# microfono_v1_rev1.net
KiCad netlist of a schematic drawn in EAGLE
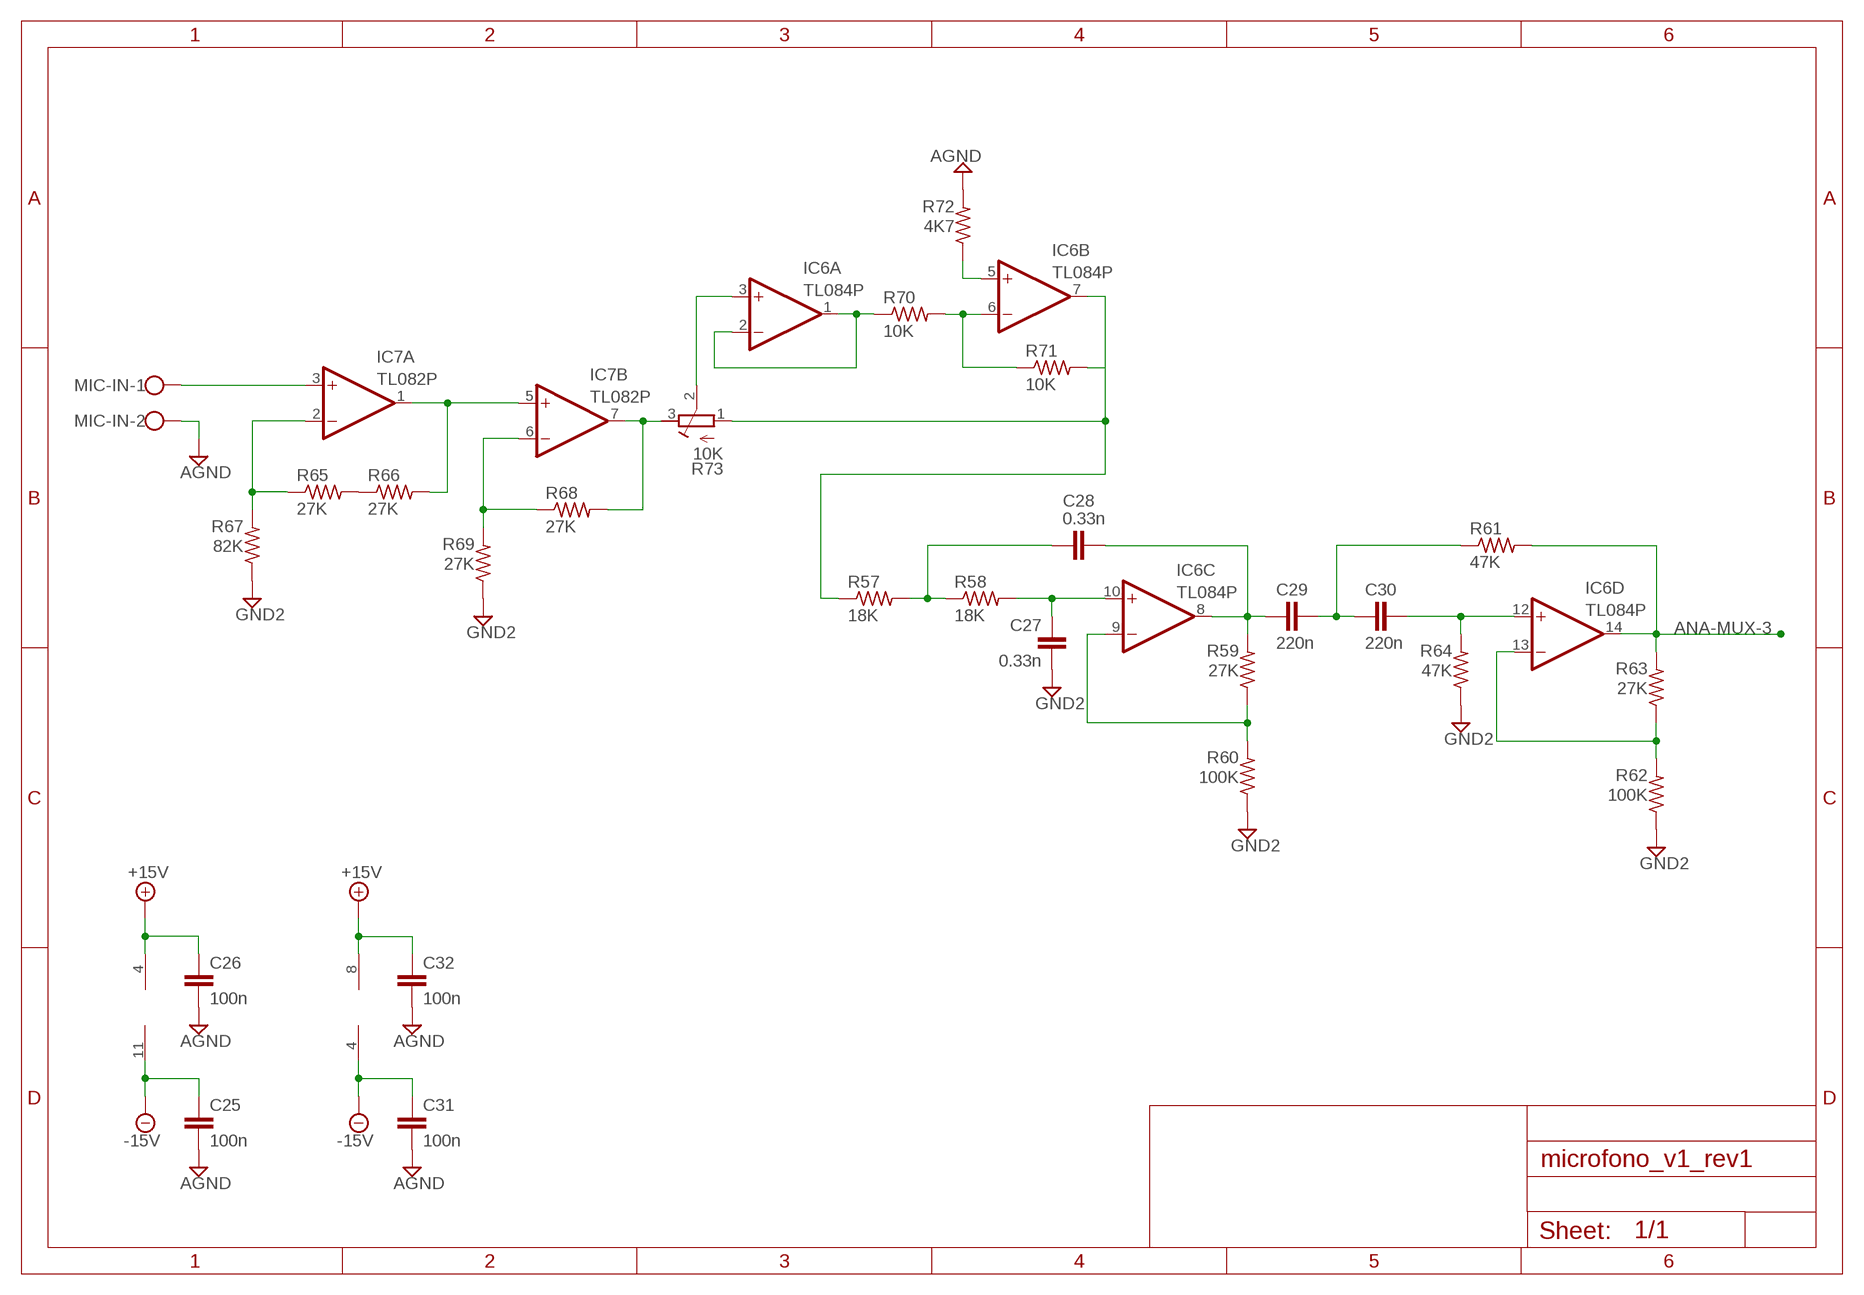
[diagram p0: schematic, sheet 1]

(export (version "E")
  (design (tool "Eeschema 10.0.6"))
  (components
    (comp (ref "C25")
      (value "100n")
      (footprint "eagle-import:C025-025X050")
      (libsource (lib "eagle-import") (part "C-EU025-025X050"))
    )
    (comp (ref "C26")
      (value "100n")
      (footprint "eagle-import:C025-025X050")
      (libsource (lib "eagle-import") (part "C-EU025-025X050"))
    )
    (comp (ref "C27")
      (value "0.33n")
      (footprint "eagle-import:C025-025X050")
      (libsource (lib "eagle-import") (part "C-EU025-025X050"))
    )
    (comp (ref "C28")
      (value "0.33n")
      (footprint "eagle-import:C025-025X050")
      (libsource (lib "eagle-import") (part "C-EU025-025X050"))
    )
    (comp (ref "C29")
      (value "220n")
      (footprint "eagle-import:C025-025X050")
      (libsource (lib "eagle-import") (part "C-EU025-025X050"))
    )
    (comp (ref "C30")
      (value "220n")
      (footprint "eagle-import:C025-025X050")
      (libsource (lib "eagle-import") (part "C-EU025-025X050"))
    )
    (comp (ref "C31")
      (value "100n")
      (footprint "eagle-import:C025-025X050")
      (libsource (lib "eagle-import") (part "C-EU025-025X050"))
    )
    (comp (ref "C32")
      (value "100n")
      (footprint "eagle-import:C025-025X050")
      (libsource (lib "eagle-import") (part "C-EU025-025X050"))
    )
    (comp (ref "IC6")
      (value "TL084P")
      (footprint "eagle-import:DIL14")
      (libsource (lib "eagle-import") (part "TL084P"))
    )
    (comp (ref "IC7")
      (value "TL082P")
      (footprint "eagle-import:DIL08")
      (libsource (lib "eagle-import") (part "TL082P"))
    )
    (comp (ref "MIC-IN")
      (value "W237-102")
      (footprint "eagle-import:W237-102")
      (fields (field (name "MPN") "237-102"))
      (libsource (lib "eagle-import") (part "W237-102"))
    )
    (comp (ref "R57")
      (value "18K")
      (footprint "eagle-import:0204_7")
      (libsource (lib "eagle-import") (part "R-US_0204/7"))
    )
    (comp (ref "R58")
      (value "18K")
      (footprint "eagle-import:0204_7")
      (libsource (lib "eagle-import") (part "R-US_0204/7"))
    )
    (comp (ref "R59")
      (value "27K")
      (footprint "eagle-import:0204_7")
      (libsource (lib "eagle-import") (part "R-US_0204/7"))
    )
    (comp (ref "R60")
      (value "100K")
      (footprint "eagle-import:0204_7")
      (libsource (lib "eagle-import") (part "R-US_0204/7"))
    )
    (comp (ref "R61")
      (value "47K")
      (footprint "eagle-import:0204_7")
      (libsource (lib "eagle-import") (part "R-US_0204/7"))
    )
    (comp (ref "R62")
      (value "100K")
      (footprint "eagle-import:0204_7")
      (libsource (lib "eagle-import") (part "R-US_0204/7"))
    )
    (comp (ref "R63")
      (value "27K")
      (footprint "eagle-import:0204_7")
      (libsource (lib "eagle-import") (part "R-US_0204/7"))
    )
    (comp (ref "R64")
      (value "47K")
      (footprint "eagle-import:0204_7")
      (libsource (lib "eagle-import") (part "R-US_0204/7"))
    )
    (comp (ref "R65")
      (value "27K")
      (footprint "eagle-import:0204_7")
      (libsource (lib "eagle-import") (part "R-US_0204/7"))
    )
    (comp (ref "R66")
      (value "27K")
      (footprint "eagle-import:0204_7")
      (libsource (lib "eagle-import") (part "R-US_0204/7"))
    )
    (comp (ref "R67")
      (value "82K")
      (footprint "eagle-import:0204_7")
      (libsource (lib "eagle-import") (part "R-US_0204/7"))
    )
    (comp (ref "R68")
      (value "27K")
      (footprint "eagle-import:0204_7")
      (libsource (lib "eagle-import") (part "R-US_0204/7"))
    )
    (comp (ref "R69")
      (value "27K")
      (footprint "eagle-import:0204_7")
      (libsource (lib "eagle-import") (part "R-US_0204/7"))
    )
    (comp (ref "R70")
      (value "10K")
      (footprint "eagle-import:0204_7")
      (libsource (lib "eagle-import") (part "R-US_0204/7"))
    )
    (comp (ref "R71")
      (value "10K")
      (footprint "eagle-import:0204_7")
      (libsource (lib "eagle-import") (part "R-US_0204/7"))
    )
    (comp (ref "R72")
      (value "4K7")
      (footprint "eagle-import:0204_7")
      (libsource (lib "eagle-import") (part "R-US_0204/7"))
    )
    (comp (ref "R73")
      (value "10K")
      (footprint "eagle-import:RTRIM64W")
      (libsource (lib "eagle-import") (part "R-TRIMM64W"))
    )
  )
  (nets
    (net (code "1") (name "+15V") (class "Default")
      (node (ref "C26") (pin "1") (pinfunction "1_1") (pintype "passive"))
      (node (ref "C32") (pin "1") (pinfunction "1_1") (pintype "passive"))
      (node (ref "IC6") (pin "4") (pinfunction "V+_4") (pintype "power_in"))
      (node (ref "IC7") (pin "8") (pinfunction "V+_8") (pintype "power_in"))
    )
    (net (code "2") (name "-15V") (class "Default")
      (node (ref "C25") (pin "1") (pinfunction "1_1") (pintype "passive"))
      (node (ref "C31") (pin "1") (pinfunction "1_1") (pintype "passive"))
      (node (ref "IC6") (pin "11") (pinfunction "V-_11") (pintype "power_in"))
      (node (ref "IC7") (pin "4") (pinfunction "V-_4") (pintype "power_in"))
    )
    (net (code "3") (name "/ANA-MUX-3") (class "Default")
      (node (ref "IC6") (pin "14") (pinfunction "OUT_14") (pintype "output"))
      (node (ref "R61") (pin "2") (pinfunction "2_2") (pintype "passive"))
      (node (ref "R63") (pin "2") (pinfunction "2_2") (pintype "passive"))
    )
    (net (code "4") (name "AGND") (class "Default")
      (node (ref "C25") (pin "2") (pinfunction "2_2") (pintype "passive"))
      (node (ref "C26") (pin "2") (pinfunction "2_2") (pintype "passive"))
      (node (ref "C31") (pin "2") (pinfunction "2_2") (pintype "passive"))
      (node (ref "C32") (pin "2") (pinfunction "2_2") (pintype "passive"))
      (node (ref "MIC-IN") (pin "2") (pinfunction "KL_2") (pintype "passive"))
      (node (ref "R72") (pin "2") (pinfunction "2_2") (pintype "passive"))
    )
    (net (code "5") (name "GND2") (class "Default")
      (node (ref "C27") (pin "2") (pinfunction "2_2") (pintype "passive"))
      (node (ref "R60") (pin "1") (pinfunction "1_1") (pintype "passive"))
      (node (ref "R62") (pin "1") (pinfunction "1_1") (pintype "passive"))
      (node (ref "R64") (pin "1") (pinfunction "1_1") (pintype "passive"))
      (node (ref "R67") (pin "1") (pinfunction "1_1") (pintype "passive"))
      (node (ref "R69") (pin "1") (pinfunction "1_1") (pintype "passive"))
    )
    (net (code "6") (name "Net-(C28-Pad1)") (class "Default")
      (node (ref "C28") (pin "1") (pinfunction "1_1") (pintype "passive"))
      (node (ref "R57") (pin "2") (pinfunction "2_2") (pintype "passive"))
      (node (ref "R58") (pin "1") (pinfunction "1_1") (pintype "passive"))
    )
    (net (code "7") (name "Net-(C29-Pad2)") (class "Default")
      (node (ref "C29") (pin "2") (pinfunction "2_2") (pintype "passive"))
      (node (ref "C30") (pin "1") (pinfunction "1_1") (pintype "passive"))
      (node (ref "R61") (pin "1") (pinfunction "1_1") (pintype "passive"))
    )
    (net (code "8") (name "Net-(IC6A-+IN)") (class "Default")
      (node (ref "IC6") (pin "3") (pinfunction "+IN_3") (pintype "input"))
      (node (ref "R73") (pin "2") (pinfunction "S_2") (pintype "passive"))
    )
    (net (code "9") (name "Net-(IC6A--IN)") (class "Default")
      (node (ref "IC6") (pin "1") (pinfunction "OUT_1") (pintype "output"))
      (node (ref "IC6") (pin "2") (pinfunction "-IN_2") (pintype "input"))
      (node (ref "R70") (pin "1") (pinfunction "1_1") (pintype "passive"))
    )
    (net (code "10") (name "Net-(IC6B-+IN)") (class "Default")
      (node (ref "IC6") (pin "5") (pinfunction "+IN_5") (pintype "input"))
      (node (ref "R72") (pin "1") (pinfunction "1_1") (pintype "passive"))
    )
    (net (code "11") (name "Net-(IC6B--IN)") (class "Default")
      (node (ref "IC6") (pin "6") (pinfunction "-IN_6") (pintype "input"))
      (node (ref "R70") (pin "2") (pinfunction "2_2") (pintype "passive"))
      (node (ref "R71") (pin "1") (pinfunction "1_1") (pintype "passive"))
    )
    (net (code "12") (name "Net-(IC6B-OUT)") (class "Default")
      (node (ref "IC6") (pin "7") (pinfunction "OUT_7") (pintype "output"))
      (node (ref "R57") (pin "1") (pinfunction "1_1") (pintype "passive"))
      (node (ref "R73") (pin "1") (pinfunction "A_1") (pintype "passive"))
    )
    (net (code "13") (name "Net-(IC6C-+IN)") (class "Default")
      (node (ref "C27") (pin "1") (pinfunction "1_1") (pintype "passive"))
      (node (ref "IC6") (pin "10") (pinfunction "+IN_10") (pintype "input"))
      (node (ref "R58") (pin "2") (pinfunction "2_2") (pintype "passive"))
    )
    (net (code "14") (name "Net-(IC6C--IN)") (class "Default")
      (node (ref "IC6") (pin "9") (pinfunction "-IN_9") (pintype "input"))
      (node (ref "R59") (pin "1") (pinfunction "1_1") (pintype "passive"))
      (node (ref "R60") (pin "2") (pinfunction "2_2") (pintype "passive"))
    )
    (net (code "15") (name "Net-(IC6C-OUT)") (class "Default")
      (node (ref "C28") (pin "2") (pinfunction "2_2") (pintype "passive"))
      (node (ref "C29") (pin "1") (pinfunction "1_1") (pintype "passive"))
      (node (ref "IC6") (pin "8") (pinfunction "OUT_8") (pintype "output"))
      (node (ref "R59") (pin "2") (pinfunction "2_2") (pintype "passive"))
    )
    (net (code "16") (name "Net-(IC6D-+IN)") (class "Default")
      (node (ref "C30") (pin "2") (pinfunction "2_2") (pintype "passive"))
      (node (ref "IC6") (pin "12") (pinfunction "+IN_12") (pintype "input"))
      (node (ref "R64") (pin "2") (pinfunction "2_2") (pintype "passive"))
    )
    (net (code "17") (name "Net-(IC6D--IN)") (class "Default")
      (node (ref "IC6") (pin "13") (pinfunction "-IN_13") (pintype "input"))
      (node (ref "R62") (pin "2") (pinfunction "2_2") (pintype "passive"))
      (node (ref "R63") (pin "1") (pinfunction "1_1") (pintype "passive"))
    )
    (net (code "18") (name "Net-(IC7A-+IN)") (class "Default")
      (node (ref "IC7") (pin "3") (pinfunction "+IN_3") (pintype "input"))
      (node (ref "MIC-IN") (pin "1") (pinfunction "KL_1") (pintype "passive"))
    )
    (net (code "19") (name "Net-(IC7A--IN)") (class "Default")
      (node (ref "IC7") (pin "2") (pinfunction "-IN_2") (pintype "input"))
      (node (ref "R65") (pin "1") (pinfunction "1_1") (pintype "passive"))
      (node (ref "R67") (pin "2") (pinfunction "2_2") (pintype "passive"))
    )
    (net (code "20") (name "Net-(IC7A-OUT)") (class "Default")
      (node (ref "IC7") (pin "1") (pinfunction "OUT_1") (pintype "output"))
      (node (ref "IC7") (pin "5") (pinfunction "+IN_5") (pintype "input"))
      (node (ref "R66") (pin "2") (pinfunction "2_2") (pintype "passive"))
    )
    (net (code "21") (name "Net-(IC7B--IN)") (class "Default")
      (node (ref "IC7") (pin "6") (pinfunction "-IN_6") (pintype "input"))
      (node (ref "R68") (pin "1") (pinfunction "1_1") (pintype "passive"))
      (node (ref "R69") (pin "2") (pinfunction "2_2") (pintype "passive"))
    )
    (net (code "22") (name "Net-(IC7B-OUT)") (class "Default")
      (node (ref "IC7") (pin "7") (pinfunction "OUT_7") (pintype "output"))
      (node (ref "R68") (pin "2") (pinfunction "2_2") (pintype "passive"))
      (node (ref "R73") (pin "3") (pinfunction "E_3") (pintype "passive"))
    )
    (net (code "23") (name "Net-(R65-Pad2)") (class "Default")
      (node (ref "R65") (pin "2") (pinfunction "2_2") (pintype "passive"))
      (node (ref "R66") (pin "1") (pinfunction "1_1") (pintype "passive"))
    )
    (net (code "24") (name "unconnected-(R71-Pad2)") (class "Default")
      (node (ref "R71") (pin "2") (pinfunction "2_2") (pintype "passive"))
    )
  )
)
